# MainBoard_PSU.net
KiCad netlist of a schematic drawn in Altium Designer
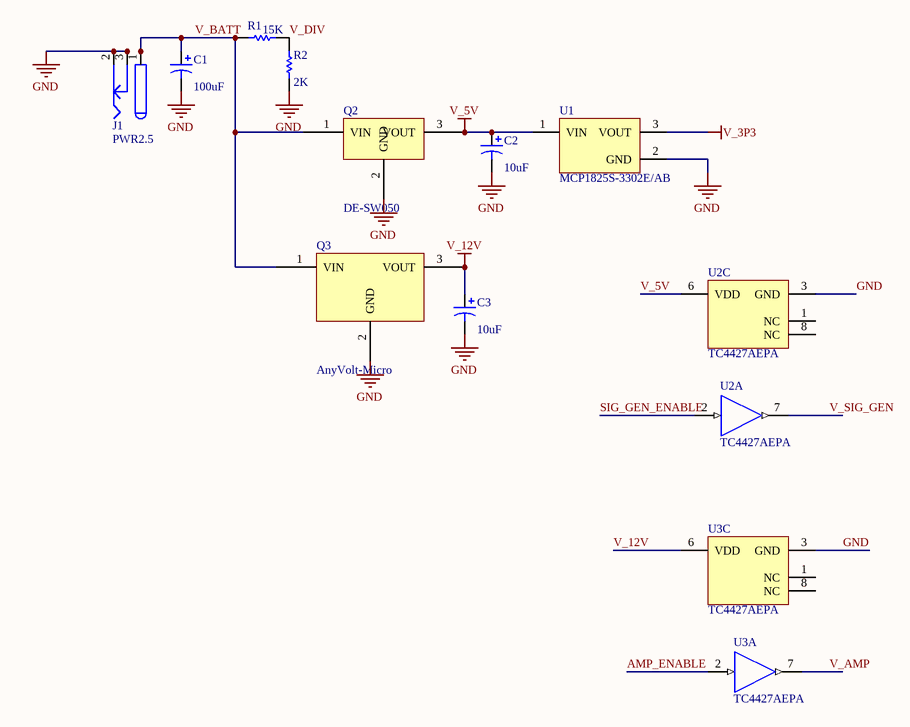
[diagram p0: MainBoard_PSU.SchDoc]

(export (version "E")
  (design (tool "Eeschema 10.0.6"))
  (components
    (comp (ref "C1")
      (value "100uF")
      (footprint "CAPPR2-5x6.8")
      (description "Polarized Capacitor (Radial)")
      (fields (field (name "Comment") "Cap Pol1") (field (name "PUBLISHER") "Altium Limited"))
      (libsource (lib "Miscellaneous Devices") (part "Cap Pol1"))
    )
    (comp (ref "C2")
      (value "10uF")
      (footprint "CAPPR2-5x6.8")
      (description "Polarized Capacitor (Radial)")
      (fields (field (name "Comment") "Cap Pol1") (field (name "PUBLISHER") "Altium Limited"))
      (libsource (lib "Miscellaneous Devices") (part "Cap Pol1"))
    )
    (comp (ref "C3")
      (value "10uF")
      (footprint "CAPPR2-5x6.8")
      (description "Polarized Capacitor (Radial)")
      (fields (field (name "Comment") "Cap Pol1") (field (name "PUBLISHER") "Altium Limited"))
      (libsource (lib "Miscellaneous Devices") (part "Cap Pol1"))
    )
    (comp (ref "J1")
      (value "PWR2.5")
      (footprint "KLD-0202")
      (description "Low Voltage Power Supply Connector")
      (fields (field (name "PUBLISHER") "Altium Limited"))
      (libsource (lib "Miscellaneous Connectors") (part "PWR2.5"))
    )
    (comp (ref "Q2")
      (value "DE-SW050")
      (footprint "TO-220")
      (libsource (lib "MainBoard_Lib") (part "DE-SW050"))
    )
    (comp (ref "Q3")
      (value "AnyVolt-Micro")
      (footprint "TO-220")
      (libsource (lib "MainBoard_Lib") (part "AnyVolt-Micro"))
    )
    (comp (ref "R1")
      (value "15K")
      (footprint "AXIAL-0.3")
      (description "Resistor")
      (fields (field (name "Comment") "Res1") (field (name "PUBLISHER") "Altium Limited"))
      (libsource (lib "Miscellaneous Devices") (part "Res1"))
    )
    (comp (ref "R2")
      (value "2K")
      (footprint "AXIAL-0.3")
      (description "Resistor")
      (fields (field (name "Comment") "Res1") (field (name "PUBLISHER") "Altium Limited"))
      (libsource (lib "Miscellaneous Devices") (part "Res1"))
    )
    (comp (ref "U1")
      (value "MCP1825S-3302E/AB")
      (footprint "TO-220-AB3")
      (description "500 mA, Low Voltage, Low Quiescent Current LDO Regulator, 3-Pin TO-220, Extended Temperature")
      (fields (field (name "PUBLISHER") "Altium Limited"))
      (libsource (lib "Microchip Power Mgt Line Regulator") (part "MCP1825S-3302E/AB"))
    )
    (comp (ref "U2")
      (value "TC4427AEPA")
      (footprint "PDIP300-PA8")
      (description "1.5A Dual High-Speed Power MOSFET Driver, Non-Inverting, Industrial Temperature")
      (fields (field (name "PUBLISHER") "Altium Limited"))
      (libsource (lib "Microchip Power Mgt MOSFET Driver") (part "TC4427AEPA"))
    )
    (comp (ref "U3")
      (value "TC4427AEPA")
      (footprint "PDIP300-PA8")
      (description "1.5A Dual High-Speed Power MOSFET Driver, Non-Inverting, Industrial Temperature")
      (fields (field (name "PUBLISHER") "Altium Limited"))
      (libsource (lib "Microchip Power Mgt MOSFET Driver") (part "TC4427AEPA"))
    )
  )
  (nets
    (net (code "1") (name "/AMP_ENABLE") (class "Default")
      (node (ref "U3") (pin "2") (pinfunction "INA_2") (pintype "input"))
    )
    (net (code "2") (name "/SIG_GEN_ENABLE") (class "Default")
      (node (ref "U2") (pin "2") (pinfunction "INA_2") (pintype "input"))
    )
    (net (code "3") (name "/V_AMP") (class "Default")
      (node (ref "U3") (pin "7") (pinfunction "OUTA_7") (pintype "output"))
    )
    (net (code "4") (name "/V_BATT") (class "Default")
      (node (ref "C1") (pin "1") (pinfunction "1_1") (pintype "passive"))
      (node (ref "J1") (pin "1") (pinfunction "1_1") (pintype "power_in"))
      (node (ref "J1") (pin "1A") (pinfunction "1A_1A") (pintype "power_in"))
      (node (ref "J1") (pin "1B") (pinfunction "1B_1B") (pintype "power_in"))
      (node (ref "Q2") (pin "1") (pinfunction "VIN_1") (pintype "power_in"))
      (node (ref "Q3") (pin "1") (pinfunction "VIN_1") (pintype "power_in"))
      (node (ref "R1") (pin "1") (pinfunction "1_1") (pintype "passive"))
    )
    (net (code "5") (name "/V_DIV") (class "Default")
      (node (ref "R1") (pin "2") (pinfunction "2_2") (pintype "passive"))
      (node (ref "R2") (pin "2") (pinfunction "2_2") (pintype "passive"))
    )
    (net (code "6") (name "/V_SIG_GEN") (class "Default")
      (node (ref "U2") (pin "7") (pinfunction "OUTA_7") (pintype "output"))
    )
    (net (code "7") (name "GND") (class "Default")
      (node (ref "C1") (pin "2") (pinfunction "2_2") (pintype "passive"))
      (node (ref "C2") (pin "2") (pinfunction "2_2") (pintype "passive"))
      (node (ref "C3") (pin "2") (pinfunction "2_2") (pintype "passive"))
      (node (ref "J1") (pin "2") (pinfunction "2_2") (pintype "power_in"))
      (node (ref "J1") (pin "2A") (pinfunction "2A_2A") (pintype "power_in"))
      (node (ref "J1") (pin "2B") (pinfunction "2B_2B") (pintype "power_in"))
      (node (ref "J1") (pin "3") (pinfunction "3_3") (pintype "power_in"))
      (node (ref "J1") (pin "3A") (pinfunction "3A_3A") (pintype "power_in"))
      (node (ref "J1") (pin "3B") (pinfunction "3B_3B") (pintype "power_in"))
      (node (ref "Q2") (pin "2") (pinfunction "GND_2") (pintype "power_in"))
      (node (ref "Q3") (pin "2") (pinfunction "GND_2") (pintype "power_in"))
      (node (ref "R2") (pin "1") (pinfunction "1_1") (pintype "passive"))
      (node (ref "U1") (pin "2") (pinfunction "GND_2") (pintype "power_in"))
      (node (ref "U2") (pin "3") (pinfunction "GND_3") (pintype "power_in"))
      (node (ref "U3") (pin "3") (pinfunction "GND_3") (pintype "power_in"))
    )
    (net (code "8") (name "V_3P3") (class "Default")
      (node (ref "U1") (pin "3") (pinfunction "VOUT_3") (pintype "power_in"))
    )
    (net (code "9") (name "V_5V") (class "Default")
      (node (ref "C2") (pin "1") (pinfunction "1_1") (pintype "passive"))
      (node (ref "Q2") (pin "3") (pinfunction "VOUT_3") (pintype "power_in"))
      (node (ref "U1") (pin "1") (pinfunction "VIN_1") (pintype "power_in"))
      (node (ref "U2") (pin "6") (pinfunction "VDD_6") (pintype "power_in"))
    )
    (net (code "10") (name "V_12V") (class "Default")
      (node (ref "C3") (pin "1") (pinfunction "1_1") (pintype "passive"))
      (node (ref "Q3") (pin "3") (pinfunction "VOUT_3") (pintype "power_in"))
      (node (ref "U3") (pin "6") (pinfunction "VDD_6") (pintype "power_in"))
    )
    (net (code "11") (name "unconnected-(U2C-NC-Pad1)") (class "Default")
      (node (ref "U2") (pin "1") (pinfunction "NC_1") (pintype "passive"))
    )
    (net (code "12") (name "unconnected-(U2C-NC-Pad8)") (class "Default")
      (node (ref "U2") (pin "8") (pinfunction "NC_8") (pintype "passive"))
    )
    (net (code "13") (name "unconnected-(U3C-NC-Pad1)") (class "Default")
      (node (ref "U3") (pin "1") (pinfunction "NC_1") (pintype "passive"))
    )
    (net (code "14") (name "unconnected-(U3C-NC-Pad8)") (class "Default")
      (node (ref "U3") (pin "8") (pinfunction "NC_8") (pintype "passive"))
    )
  )
)
